# magnetschalter.net
KiCad netlist of a schematic drawn in EAGLE
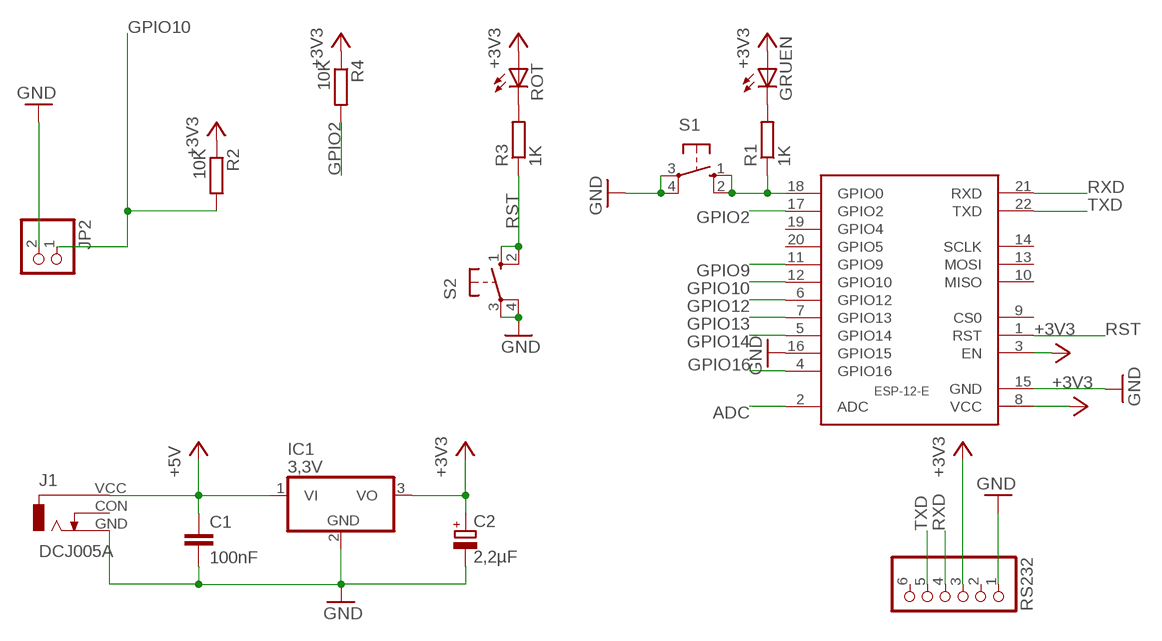
[diagram p0: schematic, sheet 1]

(export (version "E")
  (design (tool "Eeschema 10.0.6"))
  (components
    (comp (ref "C1")
      (value "100nF")
      (footprint "eagle-import:C050-030X075")
      (libsource (lib "eagle-import") (part "C-EU050-030X075"))
    )
    (comp (ref "C2")
      (value "2,2µF")
      (footprint "eagle-import:E2,5-6")
      (libsource (lib "eagle-import") (part "CPOL-EUE2.5-6"))
    )
    (comp (ref "GRUEN")
      (value "LED5MM")
      (footprint "eagle-import:LED5MM")
      (libsource (lib "eagle-import") (part "LED5MM"))
    )
    (comp (ref "IC1")
      (value "3,3V")
      (footprint "eagle-import:TO220V")
      (libsource (lib "eagle-import") (part "78TV05"))
    )
    (comp (ref "J1")
      (value "DCJ005A")
      (footprint "eagle-import:DC005A")
      (libsource (lib "eagle-import") (part "DCJ005A"))
    )
    (comp (ref "JP2")
      (value "PINHD-1X2")
      (footprint "eagle-import:1X02")
      (libsource (lib "eagle-import") (part "PINHD-1X2"))
    )
    (comp (ref "R1")
      (value "1K")
      (footprint "eagle-import:0207_10")
      (libsource (lib "eagle-import") (part "R-EU_0207/10"))
    )
    (comp (ref "R2")
      (value "10K")
      (footprint "eagle-import:0207_10")
      (libsource (lib "eagle-import") (part "R-EU_0207/10"))
    )
    (comp (ref "R3")
      (value "1K")
      (footprint "eagle-import:0207_10")
      (libsource (lib "eagle-import") (part "R-EU_0207/10"))
    )
    (comp (ref "R4")
      (value "10K")
      (footprint "eagle-import:0207_10")
      (libsource (lib "eagle-import") (part "R-EU_0207/10"))
    )
    (comp (ref "ROT")
      (value "LED5MM")
      (footprint "eagle-import:LED5MM")
      (libsource (lib "eagle-import") (part "LED5MM"))
    )
    (comp (ref "RS232")
      (value "PINHD-1X6")
      (footprint "eagle-import:1X06")
      (libsource (lib "eagle-import") (part "PINHD-1X6"))
    )
    (comp (ref "S1")
      (value "10-XX")
      (footprint "eagle-import:B3F-10XX")
      (fields (field (name "MPN") "B3F-1000"))
      (libsource (lib "eagle-import") (part "10-XX"))
    )
    (comp (ref "S2")
      (value "10-XX")
      (footprint "eagle-import:B3F-10XX")
      (fields (field (name "MPN") "B3F-1000"))
      (libsource (lib "eagle-import") (part "10-XX"))
    )
    (comp (ref "U$1")
      (value "ESP-12-E")
      (footprint "eagle-import:ESP-12-E")
      (libsource (lib "eagle-import") (part "ESP-12-E"))
    )
  )
  (nets
    (net (code "1") (name "+3V3") (class "Default")
      (node (ref "C2") (pin "+") (pinfunction "+_+") (pintype "passive"))
      (node (ref "GRUEN") (pin "A") (pinfunction "A_A") (pintype "passive"))
      (node (ref "IC1") (pin "3") (pinfunction "VO_3") (pintype "passive"))
      (node (ref "R2") (pin "1") (pinfunction "1_1") (pintype "passive"))
      (node (ref "R4") (pin "1") (pinfunction "1_1") (pintype "passive"))
      (node (ref "ROT") (pin "A") (pinfunction "A_A") (pintype "passive"))
      (node (ref "RS232") (pin "3") (pinfunction "3_3") (pintype "passive"))
      (node (ref "U$1") (pin "3") (pinfunction "EN_3") (pintype "bidirectional"))
      (node (ref "U$1") (pin "8") (pinfunction "VCC_8") (pintype "power_in"))
    )
    (net (code "2") (name "+5V") (class "Default")
      (node (ref "C1") (pin "1") (pinfunction "1_1") (pintype "passive"))
      (node (ref "IC1") (pin "1") (pinfunction "VI_1") (pintype "input"))
      (node (ref "J1") (pin "VCC") (pinfunction "1_VCC") (pintype "passive"))
    )
    (net (code "3") (name "/ADC") (class "Default")
      (node (ref "U$1") (pin "2") (pinfunction "ADC_2") (pintype "bidirectional"))
    )
    (net (code "4") (name "/GPIO2") (class "Default")
      (node (ref "R4") (pin "2") (pinfunction "2_2") (pintype "passive"))
      (node (ref "U$1") (pin "17") (pinfunction "GPIO2_17") (pintype "bidirectional"))
    )
    (net (code "5") (name "/GPIO9") (class "Default")
      (node (ref "U$1") (pin "11") (pinfunction "GPIO9_11") (pintype "bidirectional"))
    )
    (net (code "6") (name "/GPIO10") (class "Default")
      (node (ref "JP2") (pin "1") (pinfunction "1_1") (pintype "passive"))
      (node (ref "R2") (pin "2") (pinfunction "2_2") (pintype "passive"))
      (node (ref "U$1") (pin "12") (pinfunction "GPIO10_12") (pintype "bidirectional"))
    )
    (net (code "7") (name "/GPIO12") (class "Default")
      (node (ref "U$1") (pin "6") (pinfunction "GPIO12_6") (pintype "bidirectional"))
    )
    (net (code "8") (name "/GPIO13") (class "Default")
      (node (ref "U$1") (pin "7") (pinfunction "GPIO13_7") (pintype "bidirectional"))
    )
    (net (code "9") (name "/GPIO14") (class "Default")
      (node (ref "U$1") (pin "5") (pinfunction "GPIO14_5") (pintype "bidirectional"))
    )
    (net (code "10") (name "/GPIO16") (class "Default")
      (node (ref "U$1") (pin "4") (pinfunction "GPIO16_4") (pintype "bidirectional"))
    )
    (net (code "11") (name "/RST") (class "Default")
      (node (ref "R3") (pin "1") (pinfunction "1_1") (pintype "passive"))
      (node (ref "S2") (pin "1") (pinfunction "S_1") (pintype "passive"))
      (node (ref "S2") (pin "2") (pinfunction "S1_2") (pintype "passive"))
      (node (ref "U$1") (pin "1") (pinfunction "RST_1") (pintype "bidirectional"))
    )
    (net (code "12") (name "/RXD") (class "Default")
      (node (ref "RS232") (pin "4") (pinfunction "4_4") (pintype "passive"))
      (node (ref "U$1") (pin "21") (pinfunction "RXD_21") (pintype "bidirectional"))
    )
    (net (code "13") (name "/TXD") (class "Default")
      (node (ref "RS232") (pin "5") (pinfunction "5_5") (pintype "passive"))
      (node (ref "U$1") (pin "22") (pinfunction "TXD_22") (pintype "bidirectional"))
    )
    (net (code "14") (name "GND") (class "Default")
      (node (ref "C1") (pin "2") (pinfunction "2_2") (pintype "passive"))
      (node (ref "C2") (pin "-") (pinfunction "-_-") (pintype "passive"))
      (node (ref "IC1") (pin "2") (pinfunction "GND_2") (pintype "passive"))
      (node (ref "J1") (pin "GND") (pinfunction "3_GND") (pintype "passive"))
      (node (ref "JP2") (pin "2") (pinfunction "2_2") (pintype "passive"))
      (node (ref "RS232") (pin "1") (pinfunction "1_1") (pintype "passive"))
      (node (ref "S1") (pin "3") (pinfunction "P_3") (pintype "passive"))
      (node (ref "S1") (pin "4") (pinfunction "P1_4") (pintype "passive"))
      (node (ref "S2") (pin "3") (pinfunction "P_3") (pintype "passive"))
      (node (ref "S2") (pin "4") (pinfunction "P1_4") (pintype "passive"))
      (node (ref "U$1") (pin "15") (pinfunction "GND_15") (pintype "power_in"))
      (node (ref "U$1") (pin "16") (pinfunction "GPIO15_16") (pintype "bidirectional"))
    )
    (net (code "15") (name "Net-(GRUEN-C)") (class "Default")
      (node (ref "GRUEN") (pin "K") (pinfunction "C_K") (pintype "passive"))
      (node (ref "R1") (pin "2") (pinfunction "2_2") (pintype "passive"))
    )
    (net (code "16") (name "Net-(ROT-C)") (class "Default")
      (node (ref "R3") (pin "2") (pinfunction "2_2") (pintype "passive"))
      (node (ref "ROT") (pin "K") (pinfunction "C_K") (pintype "passive"))
    )
    (net (code "17") (name "Net-(S1-S)") (class "Default")
      (node (ref "R1") (pin "1") (pinfunction "1_1") (pintype "passive"))
      (node (ref "S1") (pin "1") (pinfunction "S_1") (pintype "passive"))
      (node (ref "S1") (pin "2") (pinfunction "S1_2") (pintype "passive"))
      (node (ref "U$1") (pin "18") (pinfunction "GPIO0_18") (pintype "bidirectional"))
    )
    (net (code "18") (name "unconnected-(J1-2-PadCON)") (class "Default")
      (node (ref "J1") (pin "CON") (pinfunction "2_CON") (pintype "passive"))
    )
    (net (code "19") (name "unconnected-(RS232-Pad2)") (class "Default")
      (node (ref "RS232") (pin "2") (pinfunction "2_2") (pintype "passive"))
    )
    (net (code "20") (name "unconnected-(RS232-Pad6)") (class "Default")
      (node (ref "RS232") (pin "6") (pinfunction "6_6") (pintype "passive"))
    )
    (net (code "21") (name "unconnected-(U$1-CS0-Pad9)") (class "Default")
      (node (ref "U$1") (pin "9") (pinfunction "CS0_9") (pintype "bidirectional"))
    )
    (net (code "22") (name "unconnected-(U$1-GPIO4-Pad19)") (class "Default")
      (node (ref "U$1") (pin "19") (pinfunction "GPIO4_19") (pintype "bidirectional"))
    )
    (net (code "23") (name "unconnected-(U$1-GPIO5-Pad20)") (class "Default")
      (node (ref "U$1") (pin "20") (pinfunction "GPIO5_20") (pintype "bidirectional"))
    )
    (net (code "24") (name "unconnected-(U$1-MISO-Pad10)") (class "Default")
      (node (ref "U$1") (pin "10") (pinfunction "MISO_10") (pintype "bidirectional"))
    )
    (net (code "25") (name "unconnected-(U$1-MOSI-Pad13)") (class "Default")
      (node (ref "U$1") (pin "13") (pinfunction "MOSI_13") (pintype "bidirectional"))
    )
    (net (code "26") (name "unconnected-(U$1-SCLK-Pad14)") (class "Default")
      (node (ref "U$1") (pin "14") (pinfunction "SCLK_14") (pintype "bidirectional"))
    )
  )
)
